# Main_Sheet.net
KiCad netlist of a schematic drawn in Altium Designer
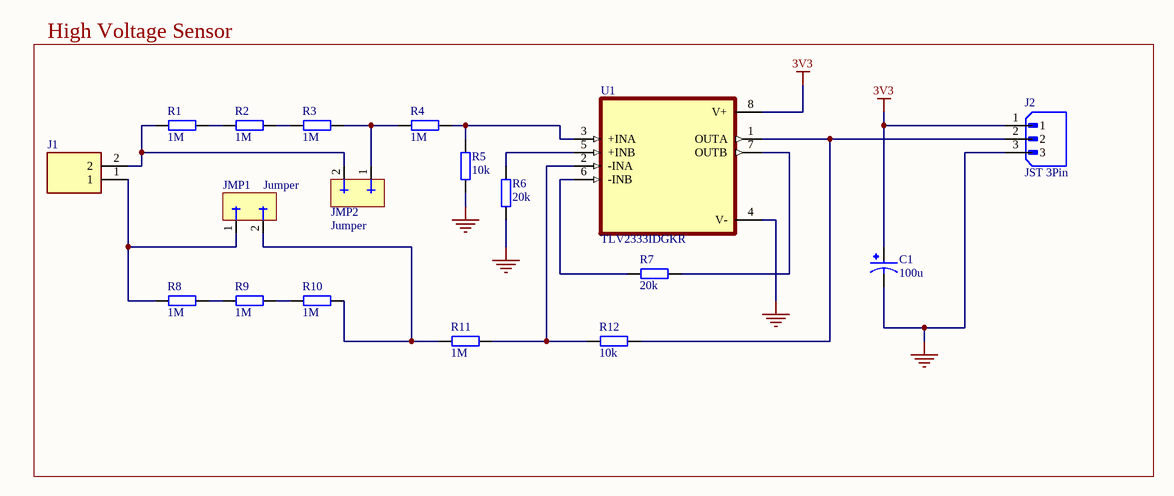
[diagram p0: Main_Sheet.SchDoc]

(export (version "E")
  (design (tool "Eeschema 10.0.6"))
  (components
    (comp (ref "C1")
      (value "100u")
      (footprint "CAP_EEEHA0J101WR")
      (fields (field (name "MF") "Panasonic Electronic") (field (name "MP") "EEE-HA0J101WR"))
      (libsource (lib "Schematic-Lib-PhilsLab") (part "EEEHA0J101WR"))
    )
    (comp (ref "J1")
      (value "~")
      (footprint "TE_282845-2")
      (description "Connector Terminal Blocks 2 POS 7.62mm Solder ST Thru-Hole")
      (fields (field (name "MP") "282845-2") (field (name "MF") "TE Connectivity"))
      (libsource (lib "Schematic-Lib-PhilsLab") (part "282845-2"))
    )
    (comp (ref "J2")
      (value "JST 3Pin")
      (footprint "JST_B3B-XH-A(LF)(SN)")
      (description "Connector Header Through Hole 3 position 0.098 (2.50mm)")
      (fields (field (name "MF") "JST Sales") (field (name "MP") "B3B-XH-A(LF)(SN)"))
      (libsource (lib "Schematic-Lib-PhilsLab") (part "JST 3Pin"))
    )
    (comp (ref "JMP1")
      (value "Jumper")
      (footprint "JMP2_TH")
      (description "Jumper 2 Pins Through-Hole DO NOT PLACE")
      (libsource (lib "") (part "JMP2_TH_1"))
    )
    (comp (ref "JMP2")
      (value "Jumper")
      (footprint "JMP2_TH")
      (description "Jumper 2 Pins Through-Hole DO NOT PLACE")
      (libsource (lib "Schematic-Lib-PhilsLab") (part "JMP2_TH"))
    )
    (comp (ref "R1")
      (value "1M")
      (footprint "RES_0805")
      (description "Resistor SMD 0805")
      (libsource (lib "Schematic-Lib-PhilsLab") (part "RES_0805"))
    )
    (comp (ref "R2")
      (value "1M")
      (footprint "RES_0805")
      (description "Resistor SMD 0805")
      (libsource (lib "Schematic-Lib-PhilsLab") (part "RES_0805"))
    )
    (comp (ref "R3")
      (value "1M")
      (footprint "RES_0805")
      (description "Resistor SMD 0805")
      (libsource (lib "Schematic-Lib-PhilsLab") (part "RES_0805"))
    )
    (comp (ref "R4")
      (value "1M")
      (footprint "RES_0805")
      (description "Resistor SMD 0805")
      (libsource (lib "Schematic-Lib-PhilsLab") (part "RES_0805"))
    )
    (comp (ref "R5")
      (value "10k")
      (footprint "RES_0805")
      (description "Resistor SMD 0805")
      (libsource (lib "Schematic-Lib-PhilsLab") (part "RES_0805"))
    )
    (comp (ref "R6")
      (value "20k")
      (footprint "RES_0805")
      (description "Resistor SMD 0805")
      (libsource (lib "Schematic-Lib-PhilsLab") (part "RES_0805"))
    )
    (comp (ref "R7")
      (value "20k")
      (footprint "RES_0805")
      (description "Resistor SMD 0805")
      (libsource (lib "Schematic-Lib-PhilsLab") (part "RES_0805"))
    )
    (comp (ref "R8")
      (value "1M")
      (footprint "RES_0805")
      (description "Resistor SMD 0805")
      (libsource (lib "Schematic-Lib-PhilsLab") (part "RES_0805"))
    )
    (comp (ref "R9")
      (value "1M")
      (footprint "RES_0805")
      (description "Resistor SMD 0805")
      (libsource (lib "Schematic-Lib-PhilsLab") (part "RES_0805"))
    )
    (comp (ref "R10")
      (value "1M")
      (footprint "RES_0805")
      (description "Resistor SMD 0805")
      (libsource (lib "Schematic-Lib-PhilsLab") (part "RES_0805"))
    )
    (comp (ref "R11")
      (value "1M")
      (footprint "RES_0805")
      (description "Resistor SMD 0805")
      (libsource (lib "Schematic-Lib-PhilsLab") (part "RES_0805"))
    )
    (comp (ref "R12")
      (value "10k")
      (footprint "RES_0805")
      (description "Resistor SMD 0805")
      (libsource (lib "Schematic-Lib-PhilsLab") (part "RES_0805"))
    )
    (comp (ref "U1")
      (value "TLV2333IDGKR")
      (footprint "SOP65P490X110-8N")
      (fields (field (name "MF") "Texas Instruments"))
      (libsource (lib "Schematic-Lib-PhilsLab") (part "TLV2333IDGKR"))
    )
  )
  (nets
    (net (code "1") (name "3V3") (class "Default")
      (node (ref "C1") (pin "1") (pinfunction "1_1") (pintype "passive"))
      (node (ref "J2") (pin "1") (pinfunction "1_1") (pintype "passive"))
      (node (ref "U1") (pin "8") (pinfunction "V+_8") (pintype "power_in"))
    )
    (net (code "2") (name "GND") (class "Default")
      (node (ref "C1") (pin "2") (pinfunction "2_2") (pintype "passive"))
      (node (ref "J2") (pin "3") (pinfunction "3_3") (pintype "passive"))
      (node (ref "R5") (pin "1") (pinfunction "1_1") (pintype "passive"))
      (node (ref "R6") (pin "1") (pinfunction "1_1") (pintype "passive"))
      (node (ref "U1") (pin "4") (pinfunction "V-_4") (pintype "power_in"))
    )
    (net (code "3") (name "Net-(J1-Pad1)") (class "Default")
      (node (ref "J1") (pin "1") (pinfunction "1_1") (pintype "passive"))
      (node (ref "JMP1") (pin "1") (pinfunction "1_1") (pintype "passive"))
      (node (ref "R8") (pin "1") (pinfunction "1_1") (pintype "passive"))
    )
    (net (code "4") (name "Net-(J1-Pad2)") (class "Default")
      (node (ref "J1") (pin "2") (pinfunction "2_2") (pintype "passive"))
      (node (ref "JMP2") (pin "2") (pinfunction "2_2") (pintype "passive"))
      (node (ref "R1") (pin "1") (pinfunction "1_1") (pintype "passive"))
    )
    (net (code "5") (name "Net-(JMP1-Pad2)") (class "Default")
      (node (ref "JMP1") (pin "2") (pinfunction "2_2") (pintype "passive"))
      (node (ref "R10") (pin "2") (pinfunction "2_2") (pintype "passive"))
      (node (ref "R11") (pin "1") (pinfunction "1_1") (pintype "passive"))
    )
    (net (code "6") (name "Net-(JMP2-Pad1)") (class "Default")
      (node (ref "JMP2") (pin "1") (pinfunction "1_1") (pintype "passive"))
      (node (ref "R3") (pin "2") (pinfunction "2_2") (pintype "passive"))
      (node (ref "R4") (pin "1") (pinfunction "1_1") (pintype "passive"))
    )
    (net (code "7") (name "Net-(R1-Pad2)") (class "Default")
      (node (ref "R1") (pin "2") (pinfunction "2_2") (pintype "passive"))
      (node (ref "R2") (pin "1") (pinfunction "1_1") (pintype "passive"))
    )
    (net (code "8") (name "Net-(R2-Pad2)") (class "Default")
      (node (ref "R2") (pin "2") (pinfunction "2_2") (pintype "passive"))
      (node (ref "R3") (pin "1") (pinfunction "1_1") (pintype "passive"))
    )
    (net (code "9") (name "Net-(R8-Pad2)") (class "Default")
      (node (ref "R8") (pin "2") (pinfunction "2_2") (pintype "passive"))
      (node (ref "R9") (pin "1") (pinfunction "1_1") (pintype "passive"))
    )
    (net (code "10") (name "Net-(R10-Pad1)") (class "Default")
      (node (ref "R10") (pin "1") (pinfunction "1_1") (pintype "passive"))
      (node (ref "R9") (pin "2") (pinfunction "2_2") (pintype "passive"))
    )
    (net (code "11") (name "Net-(U1-+INA)") (class "Default")
      (node (ref "R4") (pin "2") (pinfunction "2_2") (pintype "passive"))
      (node (ref "R5") (pin "2") (pinfunction "2_2") (pintype "passive"))
      (node (ref "U1") (pin "3") (pinfunction "+INA_3") (pintype "input"))
    )
    (net (code "12") (name "Net-(U1-+INB)") (class "Default")
      (node (ref "R6") (pin "2") (pinfunction "2_2") (pintype "passive"))
      (node (ref "U1") (pin "5") (pinfunction "+INB_5") (pintype "input"))
    )
    (net (code "13") (name "Net-(U1--INA)") (class "Default")
      (node (ref "R11") (pin "2") (pinfunction "2_2") (pintype "passive"))
      (node (ref "R12") (pin "2") (pinfunction "2_2") (pintype "passive"))
      (node (ref "U1") (pin "2") (pinfunction "-INA_2") (pintype "input"))
    )
    (net (code "14") (name "Net-(U1--INB)") (class "Default")
      (node (ref "R7") (pin "2") (pinfunction "2_2") (pintype "passive"))
      (node (ref "U1") (pin "6") (pinfunction "-INB_6") (pintype "input"))
    )
    (net (code "15") (name "Net-(U1-OUTA)") (class "Default")
      (node (ref "J2") (pin "2") (pinfunction "2_2") (pintype "passive"))
      (node (ref "R12") (pin "1") (pinfunction "1_1") (pintype "passive"))
      (node (ref "U1") (pin "1") (pinfunction "OUTA_1") (pintype "output"))
    )
    (net (code "16") (name "Net-(U1-OUTB)") (class "Default")
      (node (ref "R7") (pin "1") (pinfunction "1_1") (pintype "passive"))
      (node (ref "U1") (pin "7") (pinfunction "OUTB_7") (pintype "output"))
    )
  )
)
